# Sheet_1_2020-08-21_13-21-40.net
KiCad netlist of a schematic drawn in Altium Designer
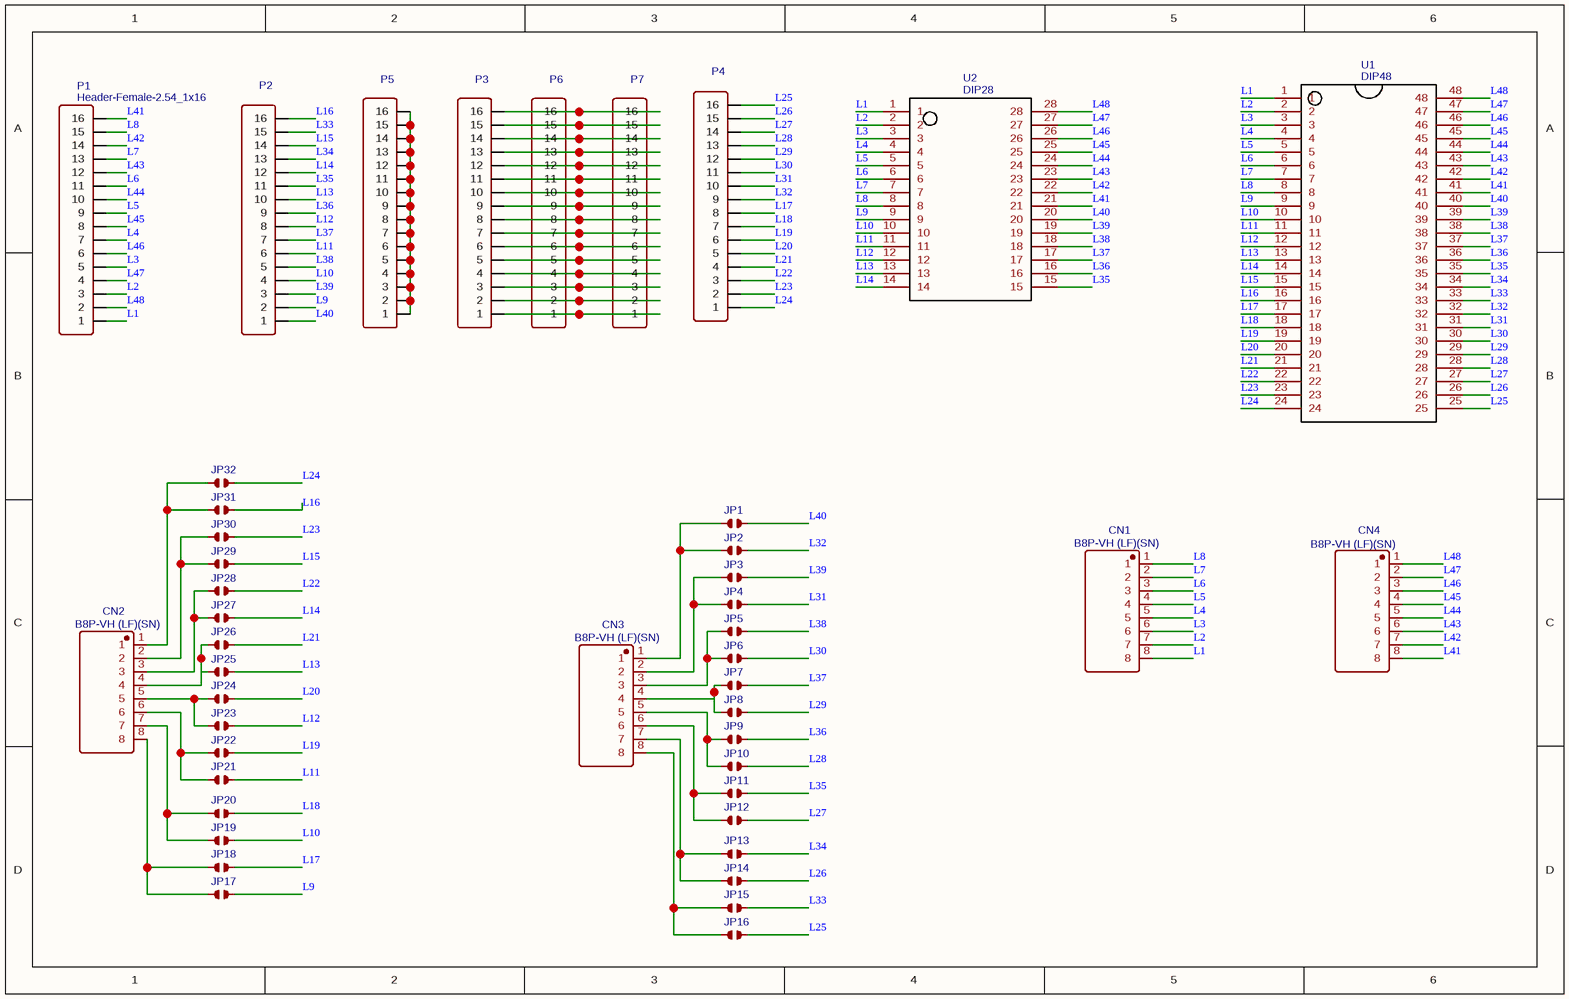
[diagram p0: Sheet_1_2020-08-21_13-21-40.schdoc]

(export (version "E")
  (design (tool "Eeschema 10.0.6"))
  (components
    (comp (ref "CN1")
      (value "B8P-VH (LF)(SN)")
      (fields (field (name "BOM_SUPPLIER PART") "C160320") (field (name "CONTRIBUTOR") "LCSC"))
      (libsource (lib "altium-import") (part "root_0_B8P-VH (LF)(SN)_"))
    )
    (comp (ref "CN2")
      (value "B8P-VH (LF)(SN)")
      (fields (field (name "BOM_SUPPLIER PART") "C160320") (field (name "CONTRIBUTOR") "LCSC"))
      (libsource (lib "altium-import") (part "root_0_B8P-VH (LF)(SN)_"))
    )
    (comp (ref "CN3")
      (value "B8P-VH (LF)(SN)")
      (fields (field (name "BOM_SUPPLIER PART") "C160320") (field (name "CONTRIBUTOR") "LCSC"))
      (libsource (lib "altium-import") (part "root_0_B8P-VH (LF)(SN)_"))
    )
    (comp (ref "CN4")
      (value "B8P-VH (LF)(SN)")
      (fields (field (name "BOM_SUPPLIER PART") "C160320") (field (name "CONTRIBUTOR") "LCSC"))
      (libsource (lib "altium-import") (part "root_0_B8P-VH (LF)(SN)_"))
    )
    (comp (ref "JP1")
      (value "Jumper pad")
      (fields (field (name "CONTRIBUTOR") "NominalAnimal"))
      (libsource (lib "altium-import") (part "root_2_Jumper pad_"))
    )
    (comp (ref "JP2")
      (value "Jumper pad")
      (fields (field (name "CONTRIBUTOR") "NominalAnimal"))
      (libsource (lib "altium-import") (part "root_2_Jumper pad_"))
    )
    (comp (ref "JP3")
      (value "Jumper pad")
      (fields (field (name "CONTRIBUTOR") "NominalAnimal"))
      (libsource (lib "altium-import") (part "root_2_Jumper pad_"))
    )
    (comp (ref "JP4")
      (value "Jumper pad")
      (fields (field (name "CONTRIBUTOR") "NominalAnimal"))
      (libsource (lib "altium-import") (part "root_2_Jumper pad_"))
    )
    (comp (ref "JP5")
      (value "Jumper pad")
      (fields (field (name "CONTRIBUTOR") "NominalAnimal"))
      (libsource (lib "altium-import") (part "root_2_Jumper pad_"))
    )
    (comp (ref "JP6")
      (value "Jumper pad")
      (fields (field (name "CONTRIBUTOR") "NominalAnimal"))
      (libsource (lib "altium-import") (part "root_2_Jumper pad_"))
    )
    (comp (ref "JP7")
      (value "Jumper pad")
      (fields (field (name "CONTRIBUTOR") "NominalAnimal"))
      (libsource (lib "altium-import") (part "root_0_Jumper pad_"))
    )
    (comp (ref "JP8")
      (value "Jumper pad")
      (fields (field (name "CONTRIBUTOR") "NominalAnimal"))
      (libsource (lib "altium-import") (part "root_0_Jumper pad_"))
    )
    (comp (ref "JP9")
      (value "Jumper pad")
      (fields (field (name "CONTRIBUTOR") "NominalAnimal"))
      (libsource (lib "altium-import") (part "root_0_Jumper pad_"))
    )
    (comp (ref "JP10")
      (value "Jumper pad")
      (fields (field (name "CONTRIBUTOR") "NominalAnimal"))
      (libsource (lib "altium-import") (part "root_0_Jumper pad_"))
    )
    (comp (ref "JP11")
      (value "Jumper pad")
      (fields (field (name "CONTRIBUTOR") "NominalAnimal"))
      (libsource (lib "altium-import") (part "root_0_Jumper pad_"))
    )
    (comp (ref "JP12")
      (value "Jumper pad")
      (fields (field (name "CONTRIBUTOR") "NominalAnimal"))
      (libsource (lib "altium-import") (part "root_0_Jumper pad_"))
    )
    (comp (ref "JP13")
      (value "Jumper pad")
      (fields (field (name "CONTRIBUTOR") "NominalAnimal"))
      (libsource (lib "altium-import") (part "root_0_Jumper pad_"))
    )
    (comp (ref "JP14")
      (value "Jumper pad")
      (fields (field (name "CONTRIBUTOR") "NominalAnimal"))
      (libsource (lib "altium-import") (part "root_0_Jumper pad_"))
    )
    (comp (ref "JP15")
      (value "Jumper pad")
      (fields (field (name "CONTRIBUTOR") "NominalAnimal"))
      (libsource (lib "altium-import") (part "root_0_Jumper pad_"))
    )
    (comp (ref "JP16")
      (value "Jumper pad")
      (fields (field (name "CONTRIBUTOR") "NominalAnimal"))
      (libsource (lib "altium-import") (part "root_0_Jumper pad_"))
    )
    (comp (ref "JP17")
      (value "Jumper pad")
      (fields (field (name "CONTRIBUTOR") "NominalAnimal"))
      (libsource (lib "altium-import") (part "root_0_Jumper pad_"))
    )
    (comp (ref "JP18")
      (value "Jumper pad")
      (fields (field (name "CONTRIBUTOR") "NominalAnimal"))
      (libsource (lib "altium-import") (part "root_0_Jumper pad_"))
    )
    (comp (ref "JP19")
      (value "Jumper pad")
      (fields (field (name "CONTRIBUTOR") "NominalAnimal"))
      (libsource (lib "altium-import") (part "root_0_Jumper pad_"))
    )
    (comp (ref "JP20")
      (value "Jumper pad")
      (fields (field (name "CONTRIBUTOR") "NominalAnimal"))
      (libsource (lib "altium-import") (part "root_0_Jumper pad_"))
    )
    (comp (ref "JP21")
      (value "Jumper pad")
      (fields (field (name "CONTRIBUTOR") "NominalAnimal"))
      (libsource (lib "altium-import") (part "root_0_Jumper pad_"))
    )
    (comp (ref "JP22")
      (value "Jumper pad")
      (fields (field (name "CONTRIBUTOR") "NominalAnimal"))
      (libsource (lib "altium-import") (part "root_0_Jumper pad_"))
    )
    (comp (ref "JP23")
      (value "Jumper pad")
      (fields (field (name "CONTRIBUTOR") "NominalAnimal"))
      (libsource (lib "altium-import") (part "root_0_Jumper pad_"))
    )
    (comp (ref "JP24")
      (value "Jumper pad")
      (fields (field (name "CONTRIBUTOR") "NominalAnimal"))
      (libsource (lib "altium-import") (part "root_0_Jumper pad_"))
    )
    (comp (ref "JP25")
      (value "Jumper pad")
      (fields (field (name "CONTRIBUTOR") "NominalAnimal"))
      (libsource (lib "altium-import") (part "root_0_Jumper pad_"))
    )
    (comp (ref "JP26")
      (value "Jumper pad")
      (fields (field (name "CONTRIBUTOR") "NominalAnimal"))
      (libsource (lib "altium-import") (part "root_0_Jumper pad_"))
    )
    (comp (ref "JP27")
      (value "Jumper pad")
      (fields (field (name "CONTRIBUTOR") "NominalAnimal"))
      (libsource (lib "altium-import") (part "root_2_Jumper pad_"))
    )
    (comp (ref "JP28")
      (value "Jumper pad")
      (fields (field (name "CONTRIBUTOR") "NominalAnimal"))
      (libsource (lib "altium-import") (part "root_2_Jumper pad_"))
    )
    (comp (ref "JP29")
      (value "Jumper pad")
      (fields (field (name "CONTRIBUTOR") "NominalAnimal"))
      (libsource (lib "altium-import") (part "root_2_Jumper pad_"))
    )
    (comp (ref "JP30")
      (value "Jumper pad")
      (fields (field (name "CONTRIBUTOR") "NominalAnimal"))
      (libsource (lib "altium-import") (part "root_2_Jumper pad_"))
    )
    (comp (ref "JP31")
      (value "Jumper pad")
      (fields (field (name "CONTRIBUTOR") "NominalAnimal"))
      (libsource (lib "altium-import") (part "root_2_Jumper pad_"))
    )
    (comp (ref "JP32")
      (value "Jumper pad")
      (fields (field (name "CONTRIBUTOR") "NominalAnimal"))
      (libsource (lib "altium-import") (part "root_2_Jumper pad_"))
    )
    (comp (ref "P1")
      (value "Header-Female-2.54_1x16")
      (fields
        (field (name "BOM_MANUFACTURER PART") "Female header1*16P pitch 2.54mm")
        (field (name "BOM_SUPPLIER PART") "C66987")
      )
      (libsource (lib "altium-import") (part "root_2_Header-Female-2.54_1x16_"))
    )
    (comp (ref "P2")
      (value "Header-Female-2.54_1x16")
      (fields
        (field (name "BOM_MANUFACTURER PART") "Female header1*16P pitch 2.54mm")
        (field (name "BOM_SUPPLIER PART") "C66987")
      )
      (libsource (lib "altium-import") (part "root_2_Header-Female-2.54_1x16_"))
    )
    (comp (ref "P3")
      (value "Header-Female-2.54_1x16")
      (fields
        (field (name "BOM_MANUFACTURER PART") "Female header1*16P pitch 2.54mm")
        (field (name "BOM_SUPPLIER PART") "C66987")
      )
      (libsource (lib "altium-import") (part "root_2_Header-Female-2.54_1x16_"))
    )
    (comp (ref "P4")
      (value "Header-Female-2.54_1x16")
      (fields
        (field (name "BOM_MANUFACTURER PART") "Female header1*16P pitch 2.54mm")
        (field (name "BOM_SUPPLIER PART") "C66987")
      )
      (libsource (lib "altium-import") (part "root_2_Header-Female-2.54_1x16_"))
    )
    (comp (ref "P5")
      (value "Header-Female-2.54_1x16")
      (fields
        (field (name "BOM_MANUFACTURER PART") "Female header1*16P pitch 2.54mm")
        (field (name "BOM_SUPPLIER PART") "C66987")
      )
      (libsource (lib "altium-import") (part "root_2_Header-Female-2.54_1x16_"))
    )
    (comp (ref "P6")
      (value "Header-Female-2.54_1x16")
      (fields
        (field (name "BOM_MANUFACTURER PART") "Female header1*16P pitch 2.54mm")
        (field (name "BOM_SUPPLIER PART") "C66987")
      )
      (libsource (lib "altium-import") (part "root_2_Header-Female-2.54_1x16_"))
    )
    (comp (ref "P7")
      (value "Header-Female-2.54_1x16")
      (fields
        (field (name "BOM_MANUFACTURER PART") "Female header1*16P pitch 2.54mm")
        (field (name "BOM_SUPPLIER PART") "C66987")
      )
      (libsource (lib "altium-import") (part "root_2_Header-Female-2.54_1x16_"))
    )
    (comp (ref "U1")
      (value "DIP48")
      (fields (field (name "CONTRIBUTOR") "Xevious"))
      (libsource (lib "altium-import") (part "root_0_DIP48_"))
    )
    (comp (ref "U2")
      (value "DIP28")
      (fields
        (field (name "BOM_MANUFACTURER PART") "New SchematicLib")
        (field (name "CONTRIBUTOR") "FYP_Squad")
      )
      (libsource (lib "altium-import") (part "root_0_DIP28_"))
    )
  )
  (nets
    (net (code "1") (name "/L1") (class "Default")
      (node (ref "CN1") (pin "8") (pinfunction "8_8") (pintype "passive"))
      (node (ref "P1") (pin "1") (pinfunction "1_1") (pintype "passive"))
      (node (ref "U1") (pin "1") (pinfunction "1_1") (pintype "passive"))
      (node (ref "U2") (pin "1") (pinfunction "1_1") (pintype "passive"))
    )
    (net (code "2") (name "/L2") (class "Default")
      (node (ref "CN1") (pin "7") (pinfunction "7_7") (pintype "passive"))
      (node (ref "P1") (pin "3") (pinfunction "3_3") (pintype "passive"))
      (node (ref "U1") (pin "2") (pinfunction "2_2") (pintype "passive"))
      (node (ref "U2") (pin "2") (pinfunction "2_2") (pintype "passive"))
    )
    (net (code "3") (name "/L3") (class "Default")
      (node (ref "CN1") (pin "6") (pinfunction "6_6") (pintype "passive"))
      (node (ref "P1") (pin "5") (pinfunction "5_5") (pintype "passive"))
      (node (ref "U1") (pin "3") (pinfunction "3_3") (pintype "passive"))
      (node (ref "U2") (pin "3") (pinfunction "3_3") (pintype "passive"))
    )
    (net (code "4") (name "/L4") (class "Default")
      (node (ref "CN1") (pin "5") (pinfunction "5_5") (pintype "passive"))
      (node (ref "P1") (pin "7") (pinfunction "7_7") (pintype "passive"))
      (node (ref "U1") (pin "4") (pinfunction "4_4") (pintype "passive"))
      (node (ref "U2") (pin "4") (pinfunction "4_4") (pintype "passive"))
    )
    (net (code "5") (name "/L5") (class "Default")
      (node (ref "CN1") (pin "4") (pinfunction "4_4") (pintype "passive"))
      (node (ref "P1") (pin "9") (pinfunction "9_9") (pintype "passive"))
      (node (ref "U1") (pin "5") (pinfunction "5_5") (pintype "passive"))
      (node (ref "U2") (pin "5") (pinfunction "5_5") (pintype "passive"))
    )
    (net (code "6") (name "/L6") (class "Default")
      (node (ref "CN1") (pin "3") (pinfunction "3_3") (pintype "passive"))
      (node (ref "P1") (pin "11") (pinfunction "11_11") (pintype "passive"))
      (node (ref "U1") (pin "6") (pinfunction "6_6") (pintype "passive"))
      (node (ref "U2") (pin "6") (pinfunction "6_6") (pintype "passive"))
    )
    (net (code "7") (name "/L7") (class "Default")
      (node (ref "CN1") (pin "2") (pinfunction "2_2") (pintype "passive"))
      (node (ref "P1") (pin "13") (pinfunction "13_13") (pintype "passive"))
      (node (ref "U1") (pin "7") (pinfunction "7_7") (pintype "passive"))
      (node (ref "U2") (pin "7") (pinfunction "7_7") (pintype "passive"))
    )
    (net (code "8") (name "/L8") (class "Default")
      (node (ref "CN1") (pin "1") (pinfunction "1_1") (pintype "passive"))
      (node (ref "P1") (pin "15") (pinfunction "15_15") (pintype "passive"))
      (node (ref "U1") (pin "8") (pinfunction "8_8") (pintype "passive"))
      (node (ref "U2") (pin "8") (pinfunction "8_8") (pintype "passive"))
    )
    (net (code "9") (name "/L9") (class "Default")
      (node (ref "JP17") (pin "2") (pinfunction "2_2") (pintype "passive"))
      (node (ref "P2") (pin "2") (pinfunction "2_2") (pintype "passive"))
      (node (ref "U1") (pin "9") (pinfunction "9_9") (pintype "passive"))
      (node (ref "U2") (pin "9") (pinfunction "9_9") (pintype "passive"))
    )
    (net (code "10") (name "/L10") (class "Default")
      (node (ref "JP19") (pin "2") (pinfunction "2_2") (pintype "passive"))
      (node (ref "P2") (pin "4") (pinfunction "4_4") (pintype "passive"))
      (node (ref "U1") (pin "10") (pinfunction "10_10") (pintype "passive"))
      (node (ref "U2") (pin "10") (pinfunction "10_10") (pintype "passive"))
    )
    (net (code "11") (name "/L11") (class "Default")
      (node (ref "JP21") (pin "2") (pinfunction "2_2") (pintype "passive"))
      (node (ref "P2") (pin "6") (pinfunction "6_6") (pintype "passive"))
      (node (ref "U1") (pin "11") (pinfunction "11_11") (pintype "passive"))
      (node (ref "U2") (pin "11") (pinfunction "11_11") (pintype "passive"))
    )
    (net (code "12") (name "/L12") (class "Default")
      (node (ref "JP23") (pin "2") (pinfunction "2_2") (pintype "passive"))
      (node (ref "P2") (pin "8") (pinfunction "8_8") (pintype "passive"))
      (node (ref "U1") (pin "12") (pinfunction "12_12") (pintype "passive"))
      (node (ref "U2") (pin "12") (pinfunction "12_12") (pintype "passive"))
    )
    (net (code "13") (name "/L13") (class "Default")
      (node (ref "JP25") (pin "2") (pinfunction "2_2") (pintype "passive"))
      (node (ref "P2") (pin "10") (pinfunction "10_10") (pintype "passive"))
      (node (ref "U1") (pin "13") (pinfunction "13_13") (pintype "passive"))
      (node (ref "U2") (pin "13") (pinfunction "13_13") (pintype "passive"))
    )
    (net (code "14") (name "/L14") (class "Default")
      (node (ref "JP27") (pin "1") (pinfunction "1_1") (pintype "passive"))
      (node (ref "P2") (pin "12") (pinfunction "12_12") (pintype "passive"))
      (node (ref "U1") (pin "14") (pinfunction "14_14") (pintype "passive"))
      (node (ref "U2") (pin "14") (pinfunction "14_14") (pintype "passive"))
    )
    (net (code "15") (name "/L15") (class "Default")
      (node (ref "JP29") (pin "1") (pinfunction "1_1") (pintype "passive"))
      (node (ref "P2") (pin "14") (pinfunction "14_14") (pintype "passive"))
      (node (ref "U1") (pin "15") (pinfunction "15_15") (pintype "passive"))
    )
    (net (code "16") (name "/L16") (class "Default")
      (node (ref "JP31") (pin "1") (pinfunction "1_1") (pintype "passive"))
      (node (ref "P2") (pin "16") (pinfunction "16_16") (pintype "passive"))
      (node (ref "U1") (pin "16") (pinfunction "16_16") (pintype "passive"))
    )
    (net (code "17") (name "/L17") (class "Default")
      (node (ref "JP18") (pin "2") (pinfunction "2_2") (pintype "passive"))
      (node (ref "P4") (pin "8") (pinfunction "8_8") (pintype "passive"))
      (node (ref "U1") (pin "17") (pinfunction "17_17") (pintype "passive"))
    )
    (net (code "18") (name "/L18") (class "Default")
      (node (ref "JP20") (pin "2") (pinfunction "2_2") (pintype "passive"))
      (node (ref "P4") (pin "7") (pinfunction "7_7") (pintype "passive"))
      (node (ref "U1") (pin "18") (pinfunction "18_18") (pintype "passive"))
    )
    (net (code "19") (name "/L19") (class "Default")
      (node (ref "JP22") (pin "2") (pinfunction "2_2") (pintype "passive"))
      (node (ref "P4") (pin "6") (pinfunction "6_6") (pintype "passive"))
      (node (ref "U1") (pin "19") (pinfunction "19_19") (pintype "passive"))
    )
    (net (code "20") (name "/L20") (class "Default")
      (node (ref "JP24") (pin "2") (pinfunction "2_2") (pintype "passive"))
      (node (ref "P4") (pin "5") (pinfunction "5_5") (pintype "passive"))
      (node (ref "U1") (pin "20") (pinfunction "20_20") (pintype "passive"))
    )
    (net (code "21") (name "/L21") (class "Default")
      (node (ref "JP26") (pin "2") (pinfunction "2_2") (pintype "passive"))
      (node (ref "P4") (pin "4") (pinfunction "4_4") (pintype "passive"))
      (node (ref "U1") (pin "21") (pinfunction "21_21") (pintype "passive"))
    )
    (net (code "22") (name "/L22") (class "Default")
      (node (ref "JP28") (pin "1") (pinfunction "1_1") (pintype "passive"))
      (node (ref "P4") (pin "3") (pinfunction "3_3") (pintype "passive"))
      (node (ref "U1") (pin "22") (pinfunction "22_22") (pintype "passive"))
    )
    (net (code "23") (name "/L23") (class "Default")
      (node (ref "JP30") (pin "1") (pinfunction "1_1") (pintype "passive"))
      (node (ref "P4") (pin "2") (pinfunction "2_2") (pintype "passive"))
      (node (ref "U1") (pin "23") (pinfunction "23_23") (pintype "passive"))
    )
    (net (code "24") (name "/L24") (class "Default")
      (node (ref "JP32") (pin "1") (pinfunction "1_1") (pintype "passive"))
      (node (ref "P4") (pin "1") (pinfunction "1_1") (pintype "passive"))
      (node (ref "U1") (pin "24") (pinfunction "24_24") (pintype "passive"))
    )
    (net (code "25") (name "/L25") (class "Default")
      (node (ref "JP16") (pin "2") (pinfunction "2_2") (pintype "passive"))
      (node (ref "P4") (pin "16") (pinfunction "16_16") (pintype "passive"))
      (node (ref "U1") (pin "25") (pinfunction "25_25") (pintype "passive"))
    )
    (net (code "26") (name "/L26") (class "Default")
      (node (ref "JP14") (pin "2") (pinfunction "2_2") (pintype "passive"))
      (node (ref "P4") (pin "15") (pinfunction "15_15") (pintype "passive"))
      (node (ref "U1") (pin "26") (pinfunction "26_26") (pintype "passive"))
    )
    (net (code "27") (name "/L27") (class "Default")
      (node (ref "JP12") (pin "2") (pinfunction "2_2") (pintype "passive"))
      (node (ref "P4") (pin "14") (pinfunction "14_14") (pintype "passive"))
      (node (ref "U1") (pin "27") (pinfunction "27_27") (pintype "passive"))
    )
    (net (code "28") (name "/L28") (class "Default")
      (node (ref "JP10") (pin "2") (pinfunction "2_2") (pintype "passive"))
      (node (ref "P4") (pin "13") (pinfunction "13_13") (pintype "passive"))
      (node (ref "U1") (pin "28") (pinfunction "28_28") (pintype "passive"))
    )
    (net (code "29") (name "/L29") (class "Default")
      (node (ref "JP8") (pin "2") (pinfunction "2_2") (pintype "passive"))
      (node (ref "P4") (pin "12") (pinfunction "12_12") (pintype "passive"))
      (node (ref "U1") (pin "29") (pinfunction "29_29") (pintype "passive"))
    )
    (net (code "30") (name "/L30") (class "Default")
      (node (ref "JP6") (pin "1") (pinfunction "1_1") (pintype "passive"))
      (node (ref "P4") (pin "11") (pinfunction "11_11") (pintype "passive"))
      (node (ref "U1") (pin "30") (pinfunction "30_30") (pintype "passive"))
    )
    (net (code "31") (name "/L31") (class "Default")
      (node (ref "JP4") (pin "1") (pinfunction "1_1") (pintype "passive"))
      (node (ref "P4") (pin "10") (pinfunction "10_10") (pintype "passive"))
      (node (ref "U1") (pin "31") (pinfunction "31_31") (pintype "passive"))
    )
    (net (code "32") (name "/L32") (class "Default")
      (node (ref "JP2") (pin "1") (pinfunction "1_1") (pintype "passive"))
      (node (ref "P4") (pin "9") (pinfunction "9_9") (pintype "passive"))
      (node (ref "U1") (pin "32") (pinfunction "32_32") (pintype "passive"))
    )
    (net (code "33") (name "/L33") (class "Default")
      (node (ref "JP15") (pin "2") (pinfunction "2_2") (pintype "passive"))
      (node (ref "P2") (pin "15") (pinfunction "15_15") (pintype "passive"))
      (node (ref "U1") (pin "33") (pinfunction "33_33") (pintype "passive"))
    )
    (net (code "34") (name "/L34") (class "Default")
      (node (ref "JP13") (pin "2") (pinfunction "2_2") (pintype "passive"))
      (node (ref "P2") (pin "13") (pinfunction "13_13") (pintype "passive"))
      (node (ref "U1") (pin "34") (pinfunction "34_34") (pintype "passive"))
    )
    (net (code "35") (name "/L35") (class "Default")
      (node (ref "JP11") (pin "2") (pinfunction "2_2") (pintype "passive"))
      (node (ref "P2") (pin "11") (pinfunction "11_11") (pintype "passive"))
      (node (ref "U1") (pin "35") (pinfunction "35_35") (pintype "passive"))
      (node (ref "U2") (pin "15") (pinfunction "15_15") (pintype "passive"))
    )
    (net (code "36") (name "/L36") (class "Default")
      (node (ref "JP9") (pin "2") (pinfunction "2_2") (pintype "passive"))
      (node (ref "P2") (pin "9") (pinfunction "9_9") (pintype "passive"))
      (node (ref "U1") (pin "36") (pinfunction "36_36") (pintype "passive"))
      (node (ref "U2") (pin "16") (pinfunction "16_16") (pintype "passive"))
    )
    (net (code "37") (name "/L37") (class "Default")
      (node (ref "JP7") (pin "2") (pinfunction "2_2") (pintype "passive"))
      (node (ref "P2") (pin "7") (pinfunction "7_7") (pintype "passive"))
      (node (ref "U1") (pin "37") (pinfunction "37_37") (pintype "passive"))
      (node (ref "U2") (pin "17") (pinfunction "17_17") (pintype "passive"))
    )
    (net (code "38") (name "/L38") (class "Default")
      (node (ref "JP5") (pin "1") (pinfunction "1_1") (pintype "passive"))
      (node (ref "P2") (pin "5") (pinfunction "5_5") (pintype "passive"))
      (node (ref "U1") (pin "38") (pinfunction "38_38") (pintype "passive"))
      (node (ref "U2") (pin "18") (pinfunction "18_18") (pintype "passive"))
    )
    (net (code "39") (name "/L39") (class "Default")
      (node (ref "JP3") (pin "1") (pinfunction "1_1") (pintype "passive"))
      (node (ref "P2") (pin "3") (pinfunction "3_3") (pintype "passive"))
      (node (ref "U1") (pin "39") (pinfunction "39_39") (pintype "passive"))
      (node (ref "U2") (pin "19") (pinfunction "19_19") (pintype "passive"))
    )
    (net (code "40") (name "/L40") (class "Default")
      (node (ref "JP1") (pin "1") (pinfunction "1_1") (pintype "passive"))
      (node (ref "P2") (pin "1") (pinfunction "1_1") (pintype "passive"))
      (node (ref "U1") (pin "40") (pinfunction "40_40") (pintype "passive"))
      (node (ref "U2") (pin "20") (pinfunction "20_20") (pintype "passive"))
    )
    (net (code "41") (name "/L41") (class "Default")
      (node (ref "CN4") (pin "8") (pinfunction "8_8") (pintype "passive"))
      (node (ref "P1") (pin "16") (pinfunction "16_16") (pintype "passive"))
      (node (ref "U1") (pin "41") (pinfunction "41_41") (pintype "passive"))
      (node (ref "U2") (pin "21") (pinfunction "21_21") (pintype "passive"))
    )
    (net (code "42") (name "/L42") (class "Default")
      (node (ref "CN4") (pin "7") (pinfunction "7_7") (pintype "passive"))
      (node (ref "P1") (pin "14") (pinfunction "14_14") (pintype "passive"))
      (node (ref "U1") (pin "42") (pinfunction "42_42") (pintype "passive"))
      (node (ref "U2") (pin "22") (pinfunction "22_22") (pintype "passive"))
    )
    (net (code "43") (name "/L43") (class "Default")
      (node (ref "CN4") (pin "6") (pinfunction "6_6") (pintype "passive"))
      (node (ref "P1") (pin "12") (pinfunction "12_12") (pintype "passive"))
      (node (ref "U1") (pin "43") (pinfunction "43_43") (pintype "passive"))
      (node (ref "U2") (pin "23") (pinfunction "23_23") (pintype "passive"))
    )
    (net (code "44") (name "/L44") (class "Default")
      (node (ref "CN4") (pin "5") (pinfunction "5_5") (pintype "passive"))
      (node (ref "P1") (pin "10") (pinfunction "10_10") (pintype "passive"))
      (node (ref "U1") (pin "44") (pinfunction "44_44") (pintype "passive"))
      (node (ref "U2") (pin "24") (pinfunction "24_24") (pintype "passive"))
    )
    (net (code "45") (name "/L45") (class "Default")
      (node (ref "CN4") (pin "4") (pinfunction "4_4") (pintype "passive"))
      (node (ref "P1") (pin "8") (pinfunction "8_8") (pintype "passive"))
      (node (ref "U1") (pin "45") (pinfunction "45_45") (pintype "passive"))
      (node (ref "U2") (pin "25") (pinfunction "25_25") (pintype "passive"))
    )
    (net (code "46") (name "/L46") (class "Default")
      (node (ref "CN4") (pin "3") (pinfunction "3_3") (pintype "passive"))
      (node (ref "P1") (pin "6") (pinfunction "6_6") (pintype "passive"))
      (node (ref "U1") (pin "46") (pinfunction "46_46") (pintype "passive"))
      (node (ref "U2") (pin "26") (pinfunction "26_26") (pintype "passive"))
    )
    (net (code "47") (name "/L47") (class "Default")
      (node (ref "CN4") (pin "2") (pinfunction "2_2") (pintype "passive"))
      (node (ref "P1") (pin "4") (pinfunction "4_4") (pintype "passive"))
      (node (ref "U1") (pin "47") (pinfunction "47_47") (pintype "passive"))
      (node (ref "U2") (pin "27") (pinfunction "27_27") (pintype "passive"))
    )
    (net (code "48") (name "/L48") (class "Default")
      (node (ref "CN4") (pin "1") (pinfunction "1_1") (pintype "passive"))
      (node (ref "P1") (pin "2") (pinfunction "2_2") (pintype "passive"))
      (node (ref "U1") (pin "48") (pinfunction "48_48") (pintype "passive"))
      (node (ref "U2") (pin "28") (pinfunction "28_28") (pintype "passive"))
    )
    (net (code "49") (name "Net-(CN2-Pad1)") (class "Default")
      (node (ref "CN2") (pin "1") (pinfunction "1_1") (pintype "passive"))
      (node (ref "JP31") (pin "2") (pinfunction "2_2") (pintype "passive"))
      (node (ref "JP32") (pin "2") (pinfunction "2_2") (pintype "passive"))
    )
    (net (code "50") (name "Net-(CN2-Pad2)") (class "Default")
      (node (ref "CN2") (pin "2") (pinfunction "2_2") (pintype "passive"))
      (node (ref "JP29") (pin "2") (pinfunction "2_2") (pintype "passive"))
      (node (ref "JP30") (pin "2") (pinfunction "2_2") (pintype "passive"))
    )
    (net (code "51") (name "Net-(CN2-Pad3)") (class "Default")
      (node (ref "CN2") (pin "3") (pinfunction "3_3") (pintype "passive"))
      (node (ref "JP27") (pin "2") (pinfunction "2_2") (pintype "passive"))
      (node (ref "JP28") (pin "2") (pinfunction "2_2") (pintype "passive"))
    )
    (net (code "52") (name "Net-(CN2-Pad4)") (class "Default")
      (node (ref "CN2") (pin "4") (pinfunction "4_4") (pintype "passive"))
      (node (ref "JP25") (pin "1") (pinfunction "1_1") (pintype "passive"))
      (node (ref "JP26") (pin "1") (pinfunction "1_1") (pintype "passive"))
    )
    (net (code "53") (name "Net-(CN2-Pad5)") (class "Default")
      (node (ref "CN2") (pin "5") (pinfunction "5_5") (pintype "passive"))
      (node (ref "JP23") (pin "1") (pinfunction "1_1") (pintype "passive"))
      (node (ref "JP24") (pin "1") (pinfunction "1_1") (pintype "passive"))
    )
    (net (code "54") (name "Net-(CN2-Pad6)") (class "Default")
      (node (ref "CN2") (pin "6") (pinfunction "6_6") (pintype "passive"))
      (node (ref "JP21") (pin "1") (pinfunction "1_1") (pintype "passive"))
      (node (ref "JP22") (pin "1") (pinfunction "1_1") (pintype "passive"))
    )
    (net (code "55") (name "Net-(CN2-Pad7)") (class "Default")
      (node (ref "CN2") (pin "7") (pinfunction "7_7") (pintype "passive"))
      (node (ref "JP19") (pin "1") (pinfunction "1_1") (pintype "passive"))
      (node (ref "JP20") (pin "1") (pinfunction "1_1") (pintype "passive"))
    )
    (net (code "56") (name "Net-(CN2-Pad8)") (class "Default")
      (node (ref "CN2") (pin "8") (pinfunction "8_8") (pintype "passive"))
      (node (ref "JP17") (pin "1") (pinfunction "1_1") (pintype "passive"))
      (node (ref "JP18") (pin "1") (pinfunction "1_1") (pintype "passive"))
    )
    (net (code "57") (name "Net-(CN3-Pad1)") (class "Default")
      (node (ref "CN3") (pin "1") (pinfunction "1_1") (pintype "passive"))
      (node (ref "JP1") (pin "2") (pinfunction "2_2") (pintype "passive"))
      (node (ref "JP2") (pin "2") (pinfunction "2_2") (pintype "passive"))
    )
    (net (code "58") (name "Net-(CN3-Pad2)") (class "Default")
      (node (ref "CN3") (pin "2") (pinfunction "2_2") (pintype "passive"))
      (node (ref "JP3") (pin "2") (pinfunction "2_2") (pintype "passive"))
      (node (ref "JP4") (pin "2") (pinfunction "2_2") (pintype "passive"))
    )
    (net (code "59") (name "Net-(CN3-Pad3)") (class "Default")
      (node (ref "CN3") (pin "3") (pinfunction "3_3") (pintype "passive"))
      (node (ref "JP5") (pin "2") (pinfunction "2_2") (pintype "passive"))
      (node (ref "JP6") (pin "2") (pinfunction "2_2") (pintype "passive"))
    )
    (net (code "60") (name "Net-(CN3-Pad4)") (class "Default")
      (node (ref "CN3") (pin "4") (pinfunction "4_4") (pintype "passive"))
      (node (ref "JP7") (pin "1") (pinfunction "1_1") (pintype "passive"))
      (node (ref "JP8") (pin "1") (pinfunction "1_1") (pintype "passive"))
    )
    (net (code "61") (name "Net-(CN3-Pad5)") (class "Default")
      (node (ref "CN3") (pin "5") (pinfunction "5_5") (pintype "passive"))
      (node (ref "JP10") (pin "1") (pinfunction "1_1") (pintype "passive"))
      (node (ref "JP9") (pin "1") (pinfunction "1_1") (pintype "passive"))
    )
    (net (code "62") (name "Net-(CN3-Pad6)") (class "Default")
      (node (ref "CN3") (pin "6") (pinfunction "6_6") (pintype "passive"))
      (node (ref "JP11") (pin "1") (pinfunction "1_1") (pintype "passive"))
      (node (ref "JP12") (pin "1") (pinfunction "1_1") (pintype "passive"))
    )
    (net (code "63") (name "Net-(CN3-Pad7)") (class "Default")
      (node (ref "CN3") (pin "7") (pinfunction "7_7") (pintype "passive"))
      (node (ref "JP13") (pin "1") (pinfunction "1_1") (pintype "passive"))
      (node (ref "JP14") (pin "1") (pinfunction "1_1") (pintype "passive"))
    )
    (net (code "64") (name "Net-(CN3-Pad8)") (class "Default")
      (node (ref "CN3") (pin "8") (pinfunction "8_8") (pintype "passive"))
      (node (ref "JP15") (pin "1") (pinfunction "1_1") (pintype "passive"))
      (node (ref "JP16") (pin "1") (pinfunction "1_1") (pintype "passive"))
    )
    (net (code "65") (name "Net-(P3-Pad1)") (class "Default")
      (node (ref "P3") (pin "1") (pinfunction "1_1") (pintype "passive"))
      (node (ref "P6") (pin "1") (pinfunction "1_1") (pintype "passive"))
      (node (ref "P7") (pin "1") (pinfunction "1_1") (pintype "passive"))
    )
    (net (code "66") (name "Net-(P3-Pad2)") (class "Default")
      (node (ref "P3") (pin "2") (pinfunction "2_2") (pintype "passive"))
      (node (ref "P6") (pin "2") (pinfunction "2_2") (pintype "passive"))
      (node (ref "P7") (pin "2") (pinfunction "2_2") (pintype "passive"))
    )
    (net (code "67") (name "Net-(P3-Pad3)") (class "Default")
      (node (ref "P3") (pin "3") (pinfunction "3_3") (pintype "passive"))
      (node (ref "P6") (pin "3") (pinfunction "3_3") (pintype "passive"))
      (node (ref "P7") (pin "3") (pinfunction "3_3") (pintype "passive"))
    )
    (net (code "68") (name "Net-(P3-Pad4)") (class "Default")
      (node (ref "P3") (pin "4") (pinfunction "4_4") (pintype "passive"))
      (node (ref "P6") (pin "4") (pinfunction "4_4") (pintype "passive"))
      (node (ref "P7") (pin "4") (pinfunction "4_4") (pintype "passive"))
    )
    (net (code "69") (name "Net-(P3-Pad5)") (class "Default")
      (node (ref "P3") (pin "5") (pinfunction "5_5") (pintype "passive"))
      (node (ref "P6") (pin "5") (pinfunction "5_5") (pintype "passive"))
      (node (ref "P7") (pin "5") (pinfunction "5_5") (pintype "passive"))
    )
    (net (code "70") (name "Net-(P3-Pad6)") (class "Default")
      (node (ref "P3") (pin "6") (pinfunction "6_6") (pintype "passive"))
      (node (ref "P6") (pin "6") (pinfunction "6_6") (pintype "passive"))
      (node (ref "P7") (pin "6") (pinfunction "6_6") (pintype "passive"))
    )
    (net (code "71") (name "Net-(P3-Pad7)") (class "Default")
      (node (ref "P3") (pin "7") (pinfunction "7_7") (pintype "passive"))
      (node (ref "P6") (pin "7") (pinfunction "7_7") (pintype "passive"))
      (node (ref "P7") (pin "7") (pinfunction "7_7") (pintype "passive"))
    )
    (net (code "72") (name "Net-(P3-Pad8)") (class "Default")
      (node (ref "P3") (pin "8") (pinfunction "8_8") (pintype "passive"))
      (node (ref "P6") (pin "8") (pinfunction "8_8") (pintype "passive"))
      (node (ref "P7") (pin "8") (pinfunction "8_8") (pintype "passive"))
    )
    (net (code "73") (name "Net-(P3-Pad9)") (class "Default")
      (node (ref "P3") (pin "9") (pinfunction "9_9") (pintype "passive"))
      (node (ref "P6") (pin "9") (pinfunction "9_9") (pintype "passive"))
      (node (ref "P7") (pin "9") (pinfunction "9_9") (pintype "passive"))
    )
    (net (code "74") (name "Net-(P3-Pad10)") (class "Default")
      (node (ref "P3") (pin "10") (pinfunction "10_10") (pintype "passive"))
      (node (ref "P6") (pin "10") (pinfunction "10_10") (pintype "passive"))
      (node (ref "P7") (pin "10") (pinfunction "10_10") (pintype "passive"))
    )
    (net (code "75") (name "Net-(P3-Pad11)") (class "Default")
      (node (ref "P3") (pin "11") (pinfunction "11_11") (pintype "passive"))
      (node (ref "P6") (pin "11") (pinfunction "11_11") (pintype "passive"))
      (node (ref "P7") (pin "11") (pinfunction "11_11") (pintype "passive"))
    )
    (net (code "76") (name "Net-(P3-Pad12)") (class "Default")
      (node (ref "P3") (pin "12") (pinfunction "12_12") (pintype "passive"))
      (node (ref "P6") (pin "12") (pinfunction "12_12") (pintype "passive"))
      (node (ref "P7") (pin "12") (pinfunction "12_12") (pintype "passive"))
    )
    (net (code "77") (name "Net-(P3-Pad13)") (class "Default")
      (node (ref "P3") (pin "13") (pinfunction "13_13") (pintype "passive"))
      (node (ref "P6") (pin "13") (pinfunction "13_13") (pintype "passive"))
      (node (ref "P7") (pin "13") (pinfunction "13_13") (pintype "passive"))
    )
    (net (code "78") (name "Net-(P3-Pad14)") (class "Default")
      (node (ref "P3") (pin "14") (pinfunction "14_14") (pintype "passive"))
      (node (ref "P6") (pin "14") (pinfunction "14_14") (pintype "passive"))
      (node (ref "P7") (pin "14") (pinfunction "14_14") (pintype "passive"))
    )
    (net (code "79") (name "Net-(P3-Pad15)") (class "Default")
      (node (ref "P3") (pin "15") (pinfunction "15_15") (pintype "passive"))
      (node (ref "P6") (pin "15") (pinfunction "15_15") (pintype "passive"))
      (node (ref "P7") (pin "15") (pinfunction "15_15") (pintype "passive"))
    )
    (net (code "80") (name "Net-(P3-Pad16)") (class "Default")
      (node (ref "P3") (pin "16") (pinfunction "16_16") (pintype "passive"))
      (node (ref "P6") (pin "16") (pinfunction "16_16") (pintype "passive"))
      (node (ref "P7") (pin "16") (pinfunction "16_16") (pintype "passive"))
    )
    (net (code "81") (name "Net-(P5-Pad1)") (class "Default")
      (node (ref "P5") (pin "1") (pinfunction "1_1") (pintype "passive"))
      (node (ref "P5") (pin "10") (pinfunction "10_10") (pintype "passive"))
      (node (ref "P5") (pin "11") (pinfunction "11_11") (pintype "passive"))
      (node (ref "P5") (pin "12") (pinfunction "12_12") (pintype "passive"))
      (node (ref "P5") (pin "13") (pinfunction "13_13") (pintype "passive"))
      (node (ref "P5") (pin "14") (pinfunction "14_14") (pintype "passive"))
      (node (ref "P5") (pin "15") (pinfunction "15_15") (pintype "passive"))
      (node (ref "P5") (pin "16") (pinfunction "16_16") (pintype "passive"))
      (node (ref "P5") (pin "2") (pinfunction "2_2") (pintype "passive"))
      (node (ref "P5") (pin "3") (pinfunction "3_3") (pintype "passive"))
      (node (ref "P5") (pin "4") (pinfunction "4_4") (pintype "passive"))
      (node (ref "P5") (pin "5") (pinfunction "5_5") (pintype "passive"))
      (node (ref "P5") (pin "6") (pinfunction "6_6") (pintype "passive"))
      (node (ref "P5") (pin "7") (pinfunction "7_7") (pintype "passive"))
      (node (ref "P5") (pin "8") (pinfunction "8_8") (pintype "passive"))
      (node (ref "P5") (pin "9") (pinfunction "9_9") (pintype "passive"))
    )
  )
)
